# output_ext-modules.net
KiCad netlist of a schematic drawn in Altium Designer
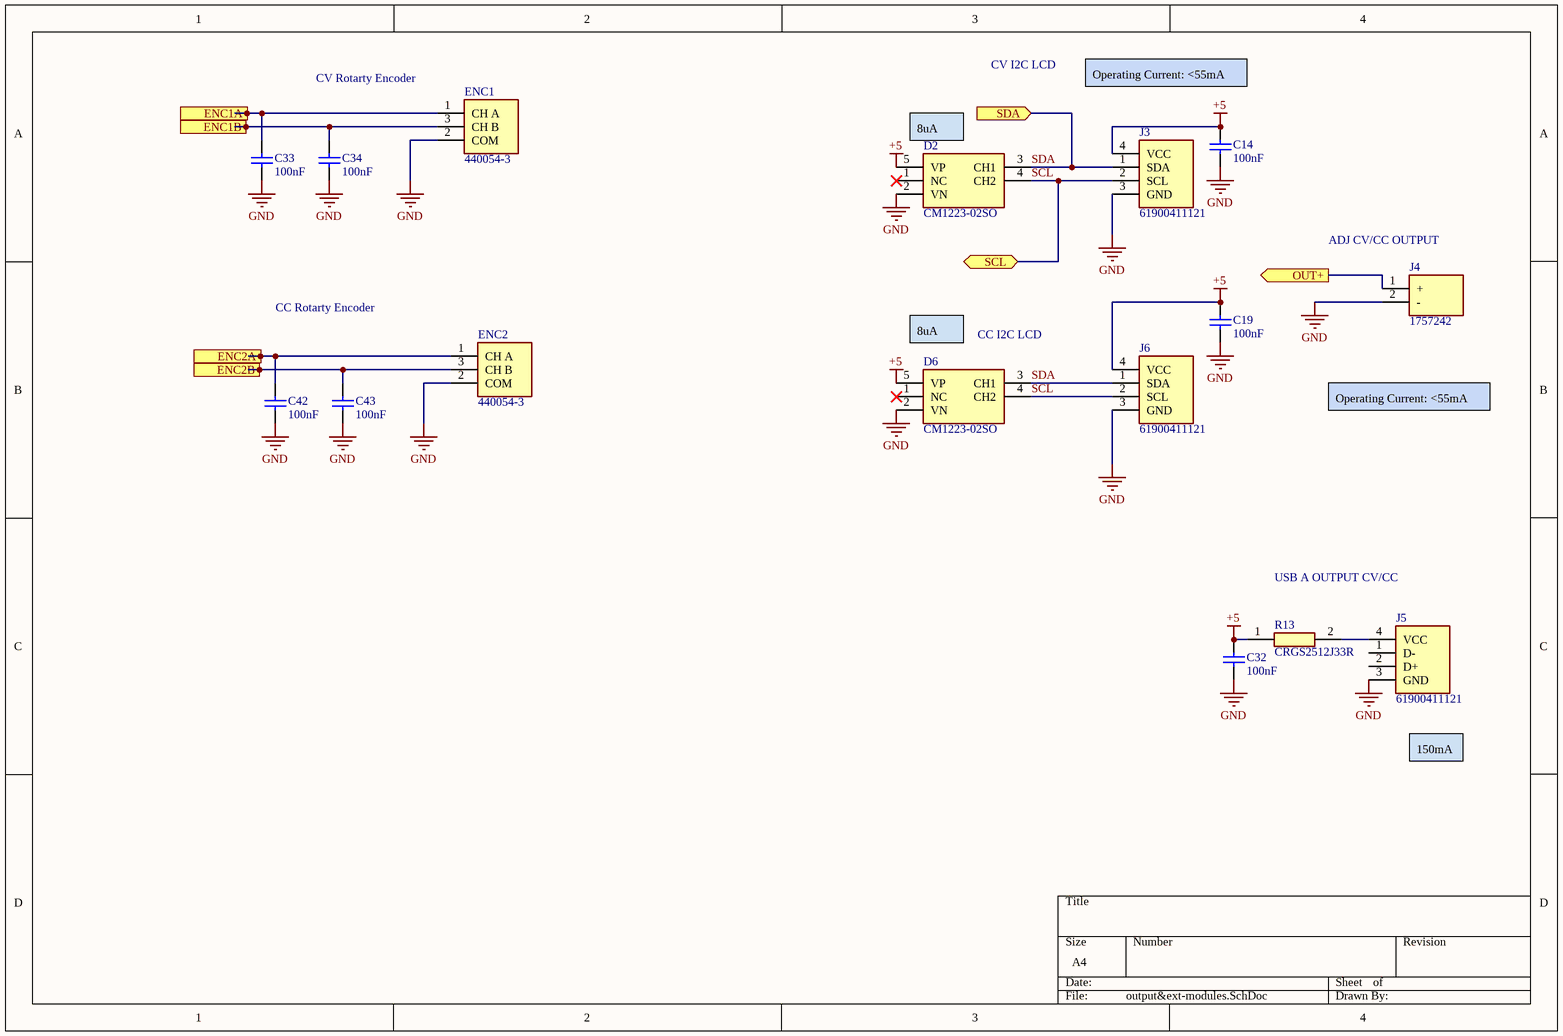
[diagram p0: output&ext-modules.SchDoc]

(export (version "E")
  (design (tool "Eeschema 10.0.6"))
  (components
    (comp (ref "C14")
      (value "100nF")
      (footprint "Cap_0603")
      (description "Capacitor")
      (fields (field (name "Comment") "Cap") (field (name "PUBLISHER") "Altium Limited"))
      (libsource (lib "cc cv power supply") (part "Cap"))
    )
    (comp (ref "C19")
      (value "100nF")
      (footprint "Cap_0603")
      (description "Capacitor")
      (fields (field (name "Comment") "Cap") (field (name "PUBLISHER") "Altium Limited"))
      (libsource (lib "cc cv power supply") (part "Cap"))
    )
    (comp (ref "C32")
      (value "100nF")
      (footprint "Cap_0603")
      (description "Capacitor")
      (fields (field (name "Comment") "Cap") (field (name "PUBLISHER") "Altium Limited"))
      (libsource (lib "cc cv power supply") (part "Cap"))
    )
    (comp (ref "C33")
      (value "100nF")
      (footprint "Cap_0603")
      (description "Capacitor")
      (fields (field (name "Comment") "Cap") (field (name "PUBLISHER") "Altium Limited"))
      (libsource (lib "cc cv power supply") (part "Cap"))
    )
    (comp (ref "C34")
      (value "100nF")
      (footprint "Cap_0603")
      (description "Capacitor")
      (fields (field (name "Comment") "Cap") (field (name "PUBLISHER") "Altium Limited"))
      (libsource (lib "cc cv power supply") (part "Cap"))
    )
    (comp (ref "C42")
      (value "100nF")
      (footprint "Cap_0603")
      (description "Capacitor")
      (fields (field (name "Comment") "Cap") (field (name "PUBLISHER") "Altium Limited"))
      (libsource (lib "cc cv power supply") (part "Cap"))
    )
    (comp (ref "C43")
      (value "100nF")
      (footprint "Cap_0603")
      (description "Capacitor")
      (fields (field (name "Comment") "Cap") (field (name "PUBLISHER") "Altium Limited"))
      (libsource (lib "cc cv power supply") (part "Cap"))
    )
    (comp (ref "D2")
      (value "CM1223-02SO")
      (footprint "SamacSys:SOT95P280X145-5N")
      (description "TVS Diode (Uni-directional)")
      (fields (field (name "MOUSER PART NUMBER") "748-CM1223-02SO"))
      (libsource (lib "SamacSys") (part "CM1223-02SO"))
    )
    (comp (ref "D6")
      (value "CM1223-02SO")
      (footprint "SamacSys:SOT95P280X145-5N")
      (description "TVS Diode (Uni-directional)")
      (fields (field (name "MOUSER PART NUMBER") "748-CM1223-02SO"))
      (libsource (lib "SamacSys") (part "CM1223-02SO"))
    )
    (comp (ref "ENC1")
      (value "440054-3")
      (footprint "SamacSys:SHDR3W50P0X200_1X3_800X470X635P")
      (description "Connector")
      (fields (field (name "MOUSER PART NUMBER") "571-440054-3"))
      (libsource (lib "SamacSys") (part "440054-3"))
    )
    (comp (ref "ENC2")
      (value "440054-3")
      (footprint "SamacSys:SHDR3W50P0X200_1X3_800X470X635P")
      (description "Connector")
      (fields (field (name "MOUSER PART NUMBER") "571-440054-3"))
      (libsource (lib "SamacSys") (part "440054-3"))
    )
    (comp (ref "J3")
      (value "61900411121")
      (footprint "SamacSys:SHDR4W64P0X254_1X4_1020X580X1175P")
      (description "Connector")
      (fields (field (name "MOUSER PART NUMBER") "710-61900411121"))
      (libsource (lib "SamacSys") (part "61900411121"))
    )
    (comp (ref "J4")
      (value "1757242")
      (footprint "SamacSys:1757242")
      (description "Connector")
      (fields (field (name "MOUSER PART NUMBER") "651-1757242"))
      (libsource (lib "*") (part "1757242"))
    )
    (comp (ref "J5")
      (value "61900411121")
      (footprint "SamacSys:SHDR4W64P0X254_1X4_1020X580X1175P")
      (description "Connector")
      (fields (field (name "MOUSER PART NUMBER") "710-61900411121"))
      (libsource (lib "SamacSys") (part "61900411121"))
    )
    (comp (ref "J6")
      (value "61900411121")
      (footprint "SamacSys:SHDR4W64P0X254_1X4_1020X580X1175P")
      (description "Connector")
      (fields (field (name "MOUSER PART NUMBER") "710-61900411121"))
      (libsource (lib "SamacSys") (part "61900411121"))
    )
    (comp (ref "R13")
      (value "CRGS2512J33R")
      (footprint "DCSupplyHupLib:RESC6432X65N")
      (description "SMD Chip Resistor, 33 ohm, ± 5%, 1.5 W, 2512 [6432 Metric], Thick Film, Anti-Surge")
      (libsource (lib "*") (part "CRGS2512J33R"))
    )
  )
  (nets
    (net (code "1") (name "+5") (class "Default")
      (node (ref "C14") (pin "1") (pinfunction "1_1") (pintype "passive"))
      (node (ref "C19") (pin "1") (pinfunction "1_1") (pintype "passive"))
      (node (ref "C32") (pin "1") (pinfunction "1_1") (pintype "passive"))
      (node (ref "D2") (pin "5") (pinfunction "VP_5") (pintype "passive"))
      (node (ref "D6") (pin "5") (pinfunction "VP_5") (pintype "passive"))
      (node (ref "J3") (pin "4") (pinfunction "VCC_4") (pintype "passive"))
      (node (ref "J6") (pin "4") (pinfunction "VCC_4") (pintype "passive"))
      (node (ref "R13") (pin "1") (pinfunction "1_1") (pintype "passive"))
    )
    (net (code "2") (name "/ENC1A") (class "Default")
      (node (ref "C33") (pin "1") (pinfunction "1_1") (pintype "passive"))
      (node (ref "ENC1") (pin "1") (pinfunction "CH_A_1") (pintype "passive"))
    )
    (net (code "3") (name "/ENC1B") (class "Default")
      (node (ref "C34") (pin "1") (pinfunction "1_1") (pintype "passive"))
      (node (ref "ENC1") (pin "3") (pinfunction "CH_B_3") (pintype "passive"))
    )
    (net (code "4") (name "/ENC2A") (class "Default")
      (node (ref "C42") (pin "1") (pinfunction "1_1") (pintype "passive"))
      (node (ref "ENC2") (pin "1") (pinfunction "CH_A_1") (pintype "passive"))
    )
    (net (code "5") (name "/ENC2B") (class "Default")
      (node (ref "C43") (pin "1") (pinfunction "1_1") (pintype "passive"))
      (node (ref "ENC2") (pin "3") (pinfunction "CH_B_3") (pintype "passive"))
    )
    (net (code "6") (name "/OUT+") (class "Default")
      (node (ref "J4") (pin "1") (pinfunction "+_1") (pintype "passive"))
    )
    (net (code "7") (name "/SCL") (class "Default")
      (node (ref "D2") (pin "4") (pinfunction "CH2_4") (pintype "passive"))
      (node (ref "D6") (pin "4") (pinfunction "CH2_4") (pintype "passive"))
      (node (ref "J3") (pin "2") (pinfunction "SCL_2") (pintype "passive"))
      (node (ref "J6") (pin "2") (pinfunction "SCL_2") (pintype "passive"))
    )
    (net (code "8") (name "/SDA") (class "Default")
      (node (ref "D2") (pin "3") (pinfunction "CH1_3") (pintype "passive"))
      (node (ref "D6") (pin "3") (pinfunction "CH1_3") (pintype "passive"))
      (node (ref "J3") (pin "1") (pinfunction "SDA_1") (pintype "passive"))
      (node (ref "J6") (pin "1") (pinfunction "SDA_1") (pintype "passive"))
    )
    (net (code "9") (name "GND") (class "Default")
      (node (ref "C14") (pin "2") (pinfunction "2_2") (pintype "passive"))
      (node (ref "C19") (pin "2") (pinfunction "2_2") (pintype "passive"))
      (node (ref "C32") (pin "2") (pinfunction "2_2") (pintype "passive"))
      (node (ref "C33") (pin "2") (pinfunction "2_2") (pintype "passive"))
      (node (ref "C34") (pin "2") (pinfunction "2_2") (pintype "passive"))
      (node (ref "C42") (pin "2") (pinfunction "2_2") (pintype "passive"))
      (node (ref "C43") (pin "2") (pinfunction "2_2") (pintype "passive"))
      (node (ref "D2") (pin "2") (pinfunction "VN_2") (pintype "passive"))
      (node (ref "D6") (pin "2") (pinfunction "VN_2") (pintype "passive"))
      (node (ref "ENC1") (pin "2") (pinfunction "COM_2") (pintype "passive"))
      (node (ref "ENC2") (pin "2") (pinfunction "COM_2") (pintype "passive"))
      (node (ref "J3") (pin "3") (pinfunction "GND_3") (pintype "passive"))
      (node (ref "J4") (pin "2") (pinfunction "-_2") (pintype "passive"))
      (node (ref "J5") (pin "3") (pinfunction "GND_3") (pintype "passive"))
      (node (ref "J6") (pin "3") (pinfunction "GND_3") (pintype "passive"))
    )
    (net (code "10") (name "Net-(J5-VCC)") (class "Default")
      (node (ref "J5") (pin "4") (pinfunction "VCC_4") (pintype "passive"))
      (node (ref "R13") (pin "2") (pinfunction "2_2") (pintype "passive"))
    )
    (net (code "11") (name "unconnected-(D2-NC-Pad1)") (class "Default")
      (node (ref "D2") (pin "1") (pinfunction "NC_1") (pintype "passive+no_connect"))
    )
    (net (code "12") (name "unconnected-(D6-NC-Pad1)") (class "Default")
      (node (ref "D6") (pin "1") (pinfunction "NC_1") (pintype "passive+no_connect"))
    )
    (net (code "13") (name "unconnected-(J5-SCL-Pad2)") (class "Default")
      (node (ref "J5") (pin "2") (pinfunction "SCL_2") (pintype "passive"))
    )
    (net (code "14") (name "unconnected-(J5-SDA-Pad1)") (class "Default")
      (node (ref "J5") (pin "1") (pinfunction "SDA_1") (pintype "passive"))
    )
  )
)
